# Sheet_708_5981.net
KiCad netlist of a schematic drawn in Altium Designer
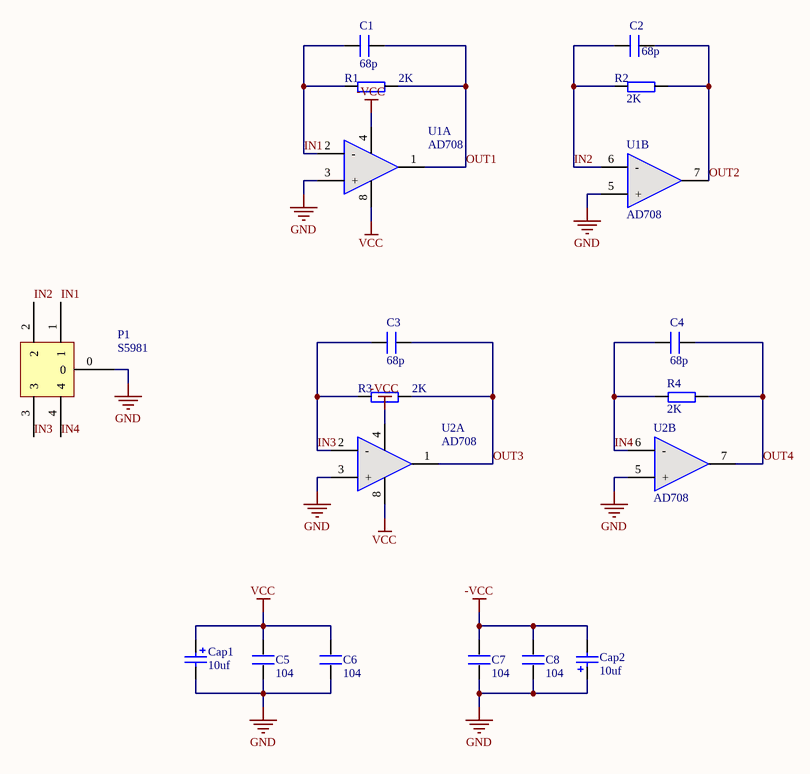
[diagram p0: Sheet_708_5981.SchDoc]

(export (version "E")
  (design (tool "Eeschema 10.0.6"))
  (components
    (comp (ref "C1") (value "68p") (footprint "0603P") (libsource (lib "阿波罗STM32F4&F7底板封装库") (part "C")))
    (comp (ref "C2") (value "68p") (footprint "0603P") (libsource (lib "阿波罗STM32F4&F7底板封装库") (part "C")))
    (comp (ref "C3") (value "68p") (footprint "0603P") (libsource (lib "阿波罗STM32F4&F7底板封装库") (part "C")))
    (comp (ref "C4") (value "68p") (footprint "0603P") (libsource (lib "阿波罗STM32F4&F7底板封装库") (part "C")))
    (comp (ref "C5") (value "104") (footprint "0603P") (libsource (lib "阿波罗STM32F4&F7底板封装库") (part "C")))
    (comp (ref "C6") (value "104") (footprint "0603P") (libsource (lib "阿波罗STM32F4&F7底板封装库") (part "C")))
    (comp (ref "C7") (value "104") (footprint "0603P") (libsource (lib "阿波罗STM32F4&F7底板封装库") (part "C")))
    (comp (ref "C8") (value "104") (footprint "0603P") (libsource (lib "阿波罗STM32F4&F7底板封装库") (part "C")))
    (comp (ref "Cap1")
      (value "10uf")
      (footprint "电容-3216")
      (description "Polarized Capacitor (Radial)")
      (fields (field (name "Comment") "10uF钽电容3216") (field (name "PUBLISHER") "Altium Limited"))
      (libsource (lib "常用元件集成库") (part "3电解电容"))
    )
    (comp (ref "Cap2")
      (value "10uf")
      (footprint "电容-3216")
      (description "Polarized Capacitor (Radial)")
      (fields (field (name "Comment") "10uF钽电容3216") (field (name "PUBLISHER") "Altium Limited"))
      (libsource (lib "常用元件集成库") (part "3电解电容"))
    )
    (comp (ref "P1") (value "S5981") (footprint "S5981") (libsource (lib "mylibProj") (part "Component_1")))
    (comp (ref "R1") (value "2K") (footprint "0603P") (libsource (lib "阿波罗STM32F4&F7底板封装库") (part "R")))
    (comp (ref "R2") (value "2K") (footprint "0603P") (libsource (lib "阿波罗STM32F4&F7底板封装库") (part "R")))
    (comp (ref "R3") (value "2K") (footprint "0603P") (libsource (lib "阿波罗STM32F4&F7底板封装库") (part "R")))
    (comp (ref "R4") (value "2K") (footprint "0603P") (libsource (lib "阿波罗STM32F4&F7底板封装库") (part "R")))
    (comp (ref "U1")
      (value "AD708")
      (footprint "NSO8_N")
      (description "双运放")
      (libsource (lib "IC集成库") (part "LM358"))
    )
    (comp (ref "U2")
      (value "AD708")
      (footprint "NSO8_N")
      (description "双运放")
      (libsource (lib "IC集成库") (part "LM358"))
    )
  )
  (nets
    (net (code "1") (name "-VCC") (class "Default")
      (node (ref "C7") (pin "2") (pintype "passive"))
      (node (ref "C8") (pin "2") (pintype "passive"))
      (node (ref "Cap2") (pin "2") (pinfunction "2_2") (pintype "passive"))
      (node (ref "U1") (pin "4") (pinfunction "V-_4") (pintype "power_in"))
      (node (ref "U2") (pin "4") (pinfunction "V-_4") (pintype "power_in"))
    )
    (net (code "2") (name "/IN1") (class "Default")
      (node (ref "C1") (pin "1") (pintype "passive"))
      (node (ref "P1") (pin "1") (pinfunction "1_1") (pintype "passive"))
      (node (ref "R1") (pin "1") (pintype "passive"))
      (node (ref "U1") (pin "2") (pinfunction "-_2") (pintype "passive"))
    )
    (net (code "3") (name "/IN2") (class "Default")
      (node (ref "C2") (pin "1") (pintype "passive"))
      (node (ref "P1") (pin "2") (pinfunction "2_2") (pintype "passive"))
      (node (ref "R2") (pin "1") (pintype "passive"))
      (node (ref "U1") (pin "6") (pinfunction "-_6") (pintype "passive"))
    )
    (net (code "4") (name "/IN3") (class "Default")
      (node (ref "C3") (pin "1") (pintype "passive"))
      (node (ref "P1") (pin "3") (pinfunction "3_3") (pintype "passive"))
      (node (ref "R3") (pin "1") (pintype "passive"))
      (node (ref "U2") (pin "2") (pinfunction "-_2") (pintype "passive"))
    )
    (net (code "5") (name "/IN4") (class "Default")
      (node (ref "C4") (pin "1") (pintype "passive"))
      (node (ref "P1") (pin "4") (pinfunction "4_4") (pintype "passive"))
      (node (ref "R4") (pin "1") (pintype "passive"))
      (node (ref "U2") (pin "6") (pinfunction "-_6") (pintype "passive"))
    )
    (net (code "6") (name "/OUT1") (class "Default")
      (node (ref "C1") (pin "2") (pintype "passive"))
      (node (ref "R1") (pin "2") (pintype "passive"))
      (node (ref "U1") (pin "1") (pinfunction "OUT1_1") (pintype "passive"))
    )
    (net (code "7") (name "/OUT2") (class "Default")
      (node (ref "C2") (pin "2") (pintype "passive"))
      (node (ref "R2") (pin "2") (pintype "passive"))
      (node (ref "U1") (pin "7") (pinfunction "OUT2_7") (pintype "passive"))
    )
    (net (code "8") (name "/OUT3") (class "Default")
      (node (ref "C3") (pin "2") (pintype "passive"))
      (node (ref "R3") (pin "2") (pintype "passive"))
      (node (ref "U2") (pin "1") (pinfunction "OUT1_1") (pintype "passive"))
    )
    (net (code "9") (name "/OUT4") (class "Default")
      (node (ref "C4") (pin "2") (pintype "passive"))
      (node (ref "R4") (pin "2") (pintype "passive"))
      (node (ref "U2") (pin "7") (pinfunction "OUT2_7") (pintype "passive"))
    )
    (net (code "10") (name "GND") (class "Default")
      (node (ref "C5") (pin "1") (pintype "passive"))
      (node (ref "C6") (pin "1") (pintype "passive"))
      (node (ref "C7") (pin "1") (pintype "passive"))
      (node (ref "C8") (pin "1") (pintype "passive"))
      (node (ref "Cap1") (pin "2") (pinfunction "2_2") (pintype "passive"))
      (node (ref "Cap2") (pin "1") (pinfunction "1_1") (pintype "passive"))
      (node (ref "P1") (pin "0") (pinfunction "0_0") (pintype "passive"))
      (node (ref "U1") (pin "3") (pinfunction "+_3") (pintype "passive"))
      (node (ref "U1") (pin "5") (pinfunction "+_5") (pintype "passive"))
      (node (ref "U2") (pin "3") (pinfunction "+_3") (pintype "passive"))
      (node (ref "U2") (pin "5") (pinfunction "+_5") (pintype "passive"))
    )
    (net (code "11") (name "VCC") (class "Default")
      (node (ref "C5") (pin "2") (pintype "passive"))
      (node (ref "C6") (pin "2") (pintype "passive"))
      (node (ref "Cap1") (pin "1") (pinfunction "1_1") (pintype "passive"))
      (node (ref "U1") (pin "8") (pinfunction "V+_8") (pintype "power_in"))
      (node (ref "U2") (pin "8") (pinfunction "V+_8") (pintype "power_in"))
    )
  )
)
